# Memory_schematic.net
KiCad netlist of a schematic drawn in Altium Designer
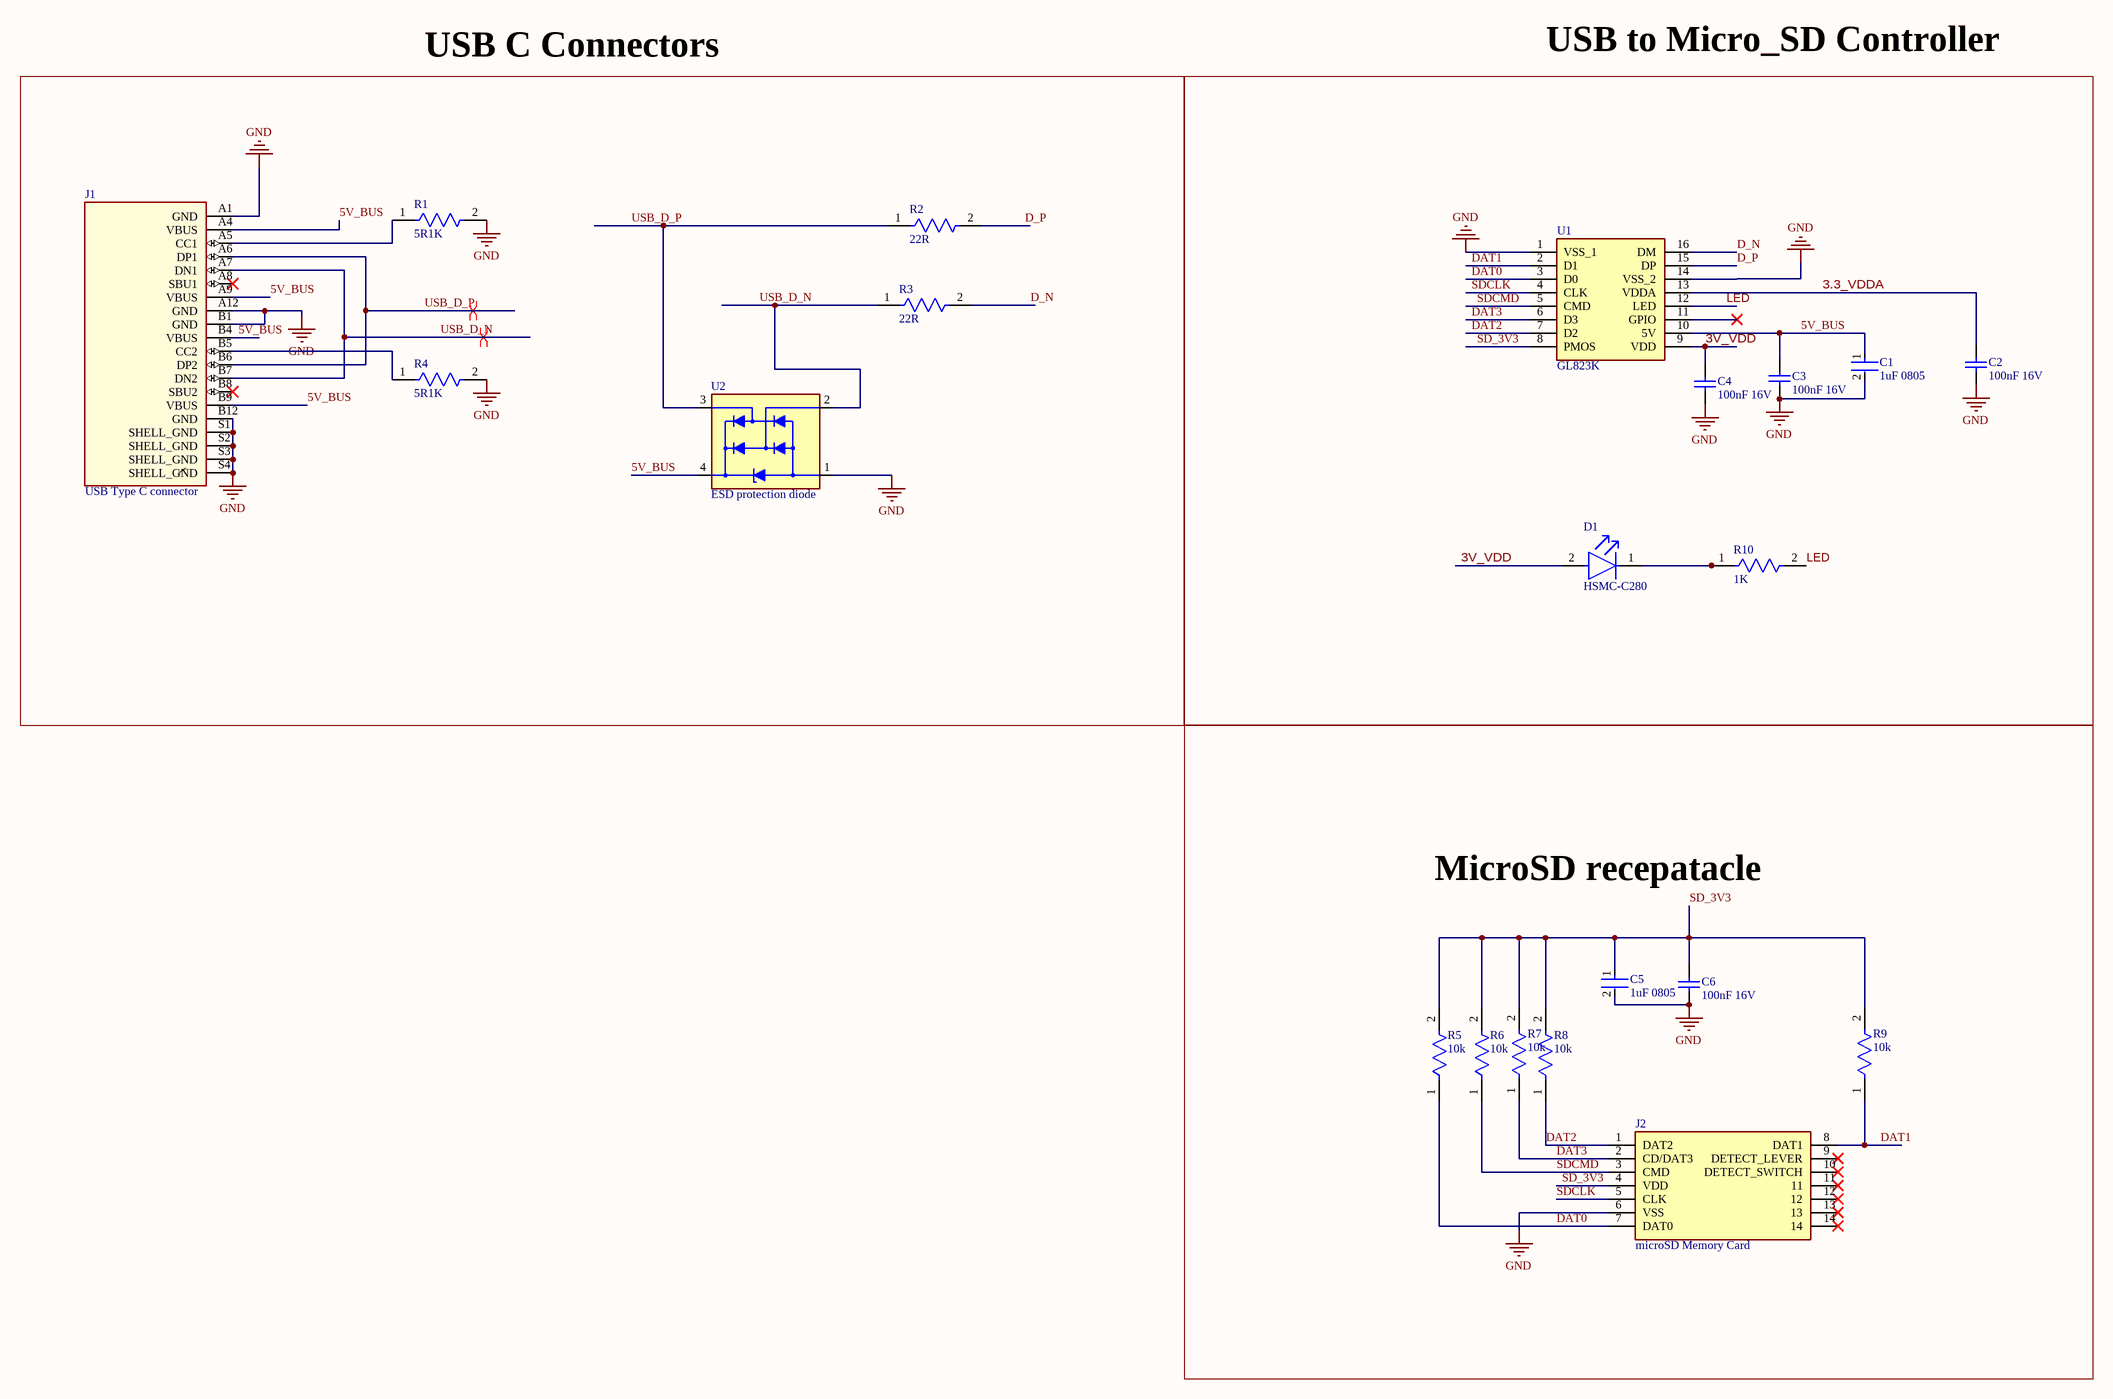
[diagram p0: Memory_schematic.SchDoc]

(export (version "E")
  (design (tool "Eeschema 10.0.6"))
  (components
    (comp (ref "C1")
      (value "1uF 0805")
      (footprint "FP-CC0805-0_85-MFG")
      (description "CC0805 1 uF X7R 10.00% 16 V")
      (fields
        (field (name "OCTOPART") "https://octopart.com/cc0805kfx7r7bb105-yageo-30261725")
        (field (name "MANUFACTURER") "Yageo")
      )
      (libsource (lib "Altium Content Vault") (part "11868f565c42a9108669ba33697ecf6"))
    )
    (comp (ref "C2")
      (value "100nF 16V")
      (footprint "CAPC0805(2012)145_M")
      (description "CAP 100nF 16V ±5% 0805 (2012 Metric) Thickness 1.45mm SMD")
      (fields (field (name "TOLERANCE") "Â±5%"))
      (libsource (lib "Altium Content Vault") (part "CAP"))
    )
    (comp (ref "C3")
      (value "100nF 16V")
      (footprint "CAPC0805(2012)145_M")
      (description "CAP 100nF 16V ±5% 0805 (2012 Metric) Thickness 1.45mm SMD")
      (fields (field (name "TOLERANCE") "Â±5%"))
      (libsource (lib "Altium Content Vault") (part "CAP"))
    )
    (comp (ref "C4")
      (value "100nF 16V")
      (footprint "CAPC0805(2012)145_M")
      (description "CAP 100nF 16V ±5% 0805 (2012 Metric) Thickness 1.45mm SMD")
      (fields (field (name "TOLERANCE") "Â±5%"))
      (libsource (lib "Altium Content Vault") (part "CAP"))
    )
    (comp (ref "C5")
      (value "1uF 0805")
      (footprint "FP-CC0805-0_85-MFG")
      (description "CC0805 1 uF X7R 10.00% 16 V")
      (fields
        (field (name "OCTOPART") "https://octopart.com/cc0805kfx7r7bb105-yageo-30261725")
        (field (name "MANUFACTURER") "Yageo")
      )
      (libsource (lib "Altium Content Vault") (part "11868f565c42a9108669ba33697ecf6"))
    )
    (comp (ref "C6")
      (value "100nF 16V")
      (footprint "CAPC0805(2012)145_M")
      (description "CAP 100nF 16V ±5% 0805 (2012 Metric) Thickness 1.45mm SMD")
      (fields (field (name "TOLERANCE") "Â±5%"))
      (libsource (lib "Altium Content Vault") (part "CAP"))
    )
    (comp (ref "D1")
      (value "HSMC-C280")
      (footprint "FP-HSMC-C280-MFG")
      (description "LED RED DIFFUSED 0402 SMD")
      (libsource (lib "Altium Content Vault") (part "8706943c75ba83719d021d2fdc84c58"))
    )
    (comp (ref "J1")
      (value "USB Type C connector")
      (footprint "CONN16_C16PIN_SHN")
      (description "https://jlcpcb.com/partdetail/ShouHan-TYPE_C_16PIN_2MD_073/C2765186?utm_source=chatgpt.com")
      (libsource (lib "Memory_card_reader_Schlib1") (part "TYPE-C 16PIN 2MD(073) SHOU HAN"))
    )
    (comp (ref "J2")
      (value "microSD Memory Card")
      (footprint "5033981892")
      (fields (field (name "MANUFACTURER") "Molex") (field (name "MANUFACTURER PART NUMBER") "503398-1892"))
      (libsource (lib "Memory_card_reader_Schlib1") (part "503398-1892"))
    )
    (comp (ref "R1")
      (value "5R1K")
      (footprint "FP-RN73R2A-IPC_C")
      (description "5.1kΩ ±0.05% 0.125W, 1/8W Chip Resistor 0805 (2012 Metric) Moisture Resistant Thin Film")
      (libsource (lib "Altium Content Vault") (part "1029c3af85768c4190bb7ad29bc67b5"))
    )
    (comp (ref "R2")
      (value "22R")
      (footprint "FP-RT0805-MFG")
      (description "RES SMD 22 OHM 1% 1/8W 0805")
      (fields
        (field (name "MANUFACTURER") "Yageo")
        (field (name "MANUFACTURER PART NUMBER") "RT0805FRD0722RL")
      )
      (libsource (lib "Altium Content Vault") (part "1029c3af85768c4190bb7ad29bc67b5"))
    )
    (comp (ref "R3")
      (value "22R")
      (footprint "FP-RT0805-MFG")
      (description "RES SMD 22 OHM 1% 1/8W 0805")
      (fields
        (field (name "MANUFACTURER") "Yageo")
        (field (name "MANUFACTURER PART NUMBER") "RT0805FRD0722RL")
      )
      (libsource (lib "Altium Content Vault") (part "1029c3af85768c4190bb7ad29bc67b5"))
    )
    (comp (ref "R4")
      (value "5R1K")
      (footprint "FP-RN73R2A-IPC_C")
      (description "5.1kΩ ±0.05% 0.125W, 1/8W Chip Resistor 0805 (2012 Metric) Moisture Resistant Thin Film")
      (libsource (lib "Altium Content Vault") (part "1029c3af85768c4190bb7ad29bc67b5"))
    )
    (comp (ref "R5")
      (value "10k")
      (footprint "FP-CRGP0805-IPC_C")
      (description "CRGP 0805 10K 1% CRGP0805F10K")
      (fields (field (name "MANUFACTURER PART NUMBER") "CRGP0805F10K") (field (name "MANUFACTURER") "TE"))
      (libsource (lib "Altium Content Vault") (part "1029c3af85768c4190bb7ad29bc67b5"))
    )
    (comp (ref "R6")
      (value "10k")
      (footprint "FP-CRGP0805-IPC_C")
      (description "CRGP 0805 10K 1% CRGP0805F10K")
      (fields (field (name "MANUFACTURER PART NUMBER") "CRGP0805F10K") (field (name "MANUFACTURER") "TE"))
      (libsource (lib "Altium Content Vault") (part "1029c3af85768c4190bb7ad29bc67b5"))
    )
    (comp (ref "R7")
      (value "10k")
      (footprint "FP-CRGP0805-IPC_C")
      (description "CRGP 0805 10K 1% CRGP0805F10K")
      (fields (field (name "MANUFACTURER PART NUMBER") "CRGP0805F10K") (field (name "MANUFACTURER") "TE"))
      (libsource (lib "Altium Content Vault") (part "1029c3af85768c4190bb7ad29bc67b5"))
    )
    (comp (ref "R8")
      (value "10k")
      (footprint "FP-CRGP0805-IPC_C")
      (description "CRGP 0805 10K 1% CRGP0805F10K")
      (fields (field (name "MANUFACTURER PART NUMBER") "CRGP0805F10K") (field (name "MANUFACTURER") "TE"))
      (libsource (lib "Altium Content Vault") (part "1029c3af85768c4190bb7ad29bc67b5"))
    )
    (comp (ref "R9")
      (value "10k")
      (footprint "FP-CRGP0805-IPC_C")
      (description "CRGP 0805 10K 1% CRGP0805F10K")
      (fields (field (name "MANUFACTURER PART NUMBER") "CRGP0805F10K") (field (name "MANUFACTURER") "TE"))
      (libsource (lib "Altium Content Vault") (part "1029c3af85768c4190bb7ad29bc67b5"))
    )
    (comp (ref "R10")
      (value "1K")
      (footprint "FP-RN73R2A-IPC_A")
      (description "1kΩ ±0.1% 0.125W, 1/8W Chip Resistor 0805 (2012 Metric) Moisture Resistant Thin Film")
      (libsource (lib "Altium Content Vault") (part "1029c3af85768c4190bb7ad29bc67b5"))
    )
    (comp (ref "U1")
      (value "GL823K")
      (footprint "SOP64P600X175-16N")
      (description "USB 2.0 card reader controller")
      (libsource (lib "Memory_card_reader_Schlib1") (part "GL823K-HCY04"))
    )
    (comp (ref "U2")
      (value "ESD protection diode")
      (footprint "SOT190P230X110-4N")
      (description "PRTR Series 9 V 1 pF Rail-to-Rail ESD Protection Diode - SOT-143B")
      (fields
        (field (name "MANUFACTURER") "Nexperia")
        (field (name "MANUFACTURER PART NUMBER") "PRTR5V0U2X,215")
      )
      (libsource (lib "Memory_card_reader_Schlib1") (part "PRTR5V0U2X,215"))
    )
  )
  (nets
    (net (code "1") (name "/3.3_VDDA") (class "Default")
      (node (ref "C2") (pin "2") (pinfunction "2_2") (pintype "passive"))
      (node (ref "U1") (pin "13") (pinfunction "VDDA_13") (pintype "passive"))
    )
    (net (code "2") (name "/3V_VDD") (class "Default")
      (node (ref "C4") (pin "2") (pinfunction "2_2") (pintype "passive"))
      (node (ref "D1") (pin "2") (pinfunction "A_2") (pintype "passive"))
      (node (ref "U1") (pin "9") (pinfunction "VDD_9") (pintype "passive"))
    )
    (net (code "3") (name "/5V_BUS") (class "Default")
      (node (ref "C1") (pin "1") (pinfunction "1_1") (pintype "passive"))
      (node (ref "C3") (pin "2") (pinfunction "2_2") (pintype "passive"))
      (node (ref "J1") (pin "A4") (pinfunction "VBUS_A4") (pintype "power_in"))
      (node (ref "J1") (pin "A9") (pinfunction "VBUS_A9") (pintype "power_in"))
      (node (ref "J1") (pin "B4") (pinfunction "VBUS_B4") (pintype "power_in"))
      (node (ref "J1") (pin "B9") (pinfunction "VBUS_B9") (pintype "power_in"))
      (node (ref "U1") (pin "10") (pinfunction "5V_10") (pintype "passive"))
      (node (ref "U2") (pin "4") (pinfunction "VCC_4") (pintype "passive"))
    )
    (net (code "4") (name "/DAT0") (class "Default")
      (node (ref "J2") (pin "7") (pinfunction "DAT0_7") (pintype "passive"))
      (node (ref "R5") (pin "1") (pinfunction "1_1") (pintype "passive"))
      (node (ref "U1") (pin "3") (pinfunction "D0_3") (pintype "passive"))
    )
    (net (code "5") (name "/DAT1") (class "Default")
      (node (ref "J2") (pin "8") (pinfunction "DAT1_8") (pintype "passive"))
      (node (ref "R9") (pin "1") (pinfunction "1_1") (pintype "passive"))
      (node (ref "U1") (pin "2") (pinfunction "D1_2") (pintype "passive"))
    )
    (net (code "6") (name "/DAT2") (class "Default")
      (node (ref "J2") (pin "1") (pinfunction "DAT2_1") (pintype "passive"))
      (node (ref "R8") (pin "1") (pinfunction "1_1") (pintype "passive"))
      (node (ref "U1") (pin "7") (pinfunction "D2_7") (pintype "passive"))
    )
    (net (code "7") (name "/DAT3") (class "Default")
      (node (ref "J2") (pin "2") (pinfunction "CD/DAT3_2") (pintype "passive"))
      (node (ref "R7") (pin "1") (pinfunction "1_1") (pintype "passive"))
      (node (ref "U1") (pin "6") (pinfunction "D3_6") (pintype "passive"))
    )
    (net (code "8") (name "/D_N") (class "Default")
      (node (ref "R3") (pin "2") (pinfunction "2_2") (pintype "passive"))
      (node (ref "U1") (pin "16") (pinfunction "DM_16") (pintype "passive"))
    )
    (net (code "9") (name "/D_P") (class "Default")
      (node (ref "R2") (pin "2") (pinfunction "2_2") (pintype "passive"))
      (node (ref "U1") (pin "15") (pinfunction "DP_15") (pintype "passive"))
    )
    (net (code "10") (name "/LED") (class "Default")
      (node (ref "R10") (pin "2") (pinfunction "2_2") (pintype "passive"))
      (node (ref "U1") (pin "12") (pinfunction "LED_12") (pintype "passive"))
    )
    (net (code "11") (name "/SDCLK") (class "Default")
      (node (ref "J2") (pin "5") (pinfunction "CLK_5") (pintype "passive"))
      (node (ref "U1") (pin "4") (pinfunction "CLK_4") (pintype "passive"))
    )
    (net (code "12") (name "/SDCMD") (class "Default")
      (node (ref "J2") (pin "3") (pinfunction "CMD_3") (pintype "passive"))
      (node (ref "R6") (pin "1") (pinfunction "1_1") (pintype "passive"))
      (node (ref "U1") (pin "5") (pinfunction "CMD_5") (pintype "passive"))
    )
    (net (code "13") (name "/SD_3V3") (class "Default")
      (node (ref "C5") (pin "1") (pinfunction "1_1") (pintype "passive"))
      (node (ref "C6") (pin "2") (pinfunction "2_2") (pintype "passive"))
      (node (ref "J2") (pin "4") (pinfunction "VDD_4") (pintype "passive"))
      (node (ref "R5") (pin "2") (pinfunction "2_2") (pintype "passive"))
      (node (ref "R6") (pin "2") (pinfunction "2_2") (pintype "passive"))
      (node (ref "R7") (pin "2") (pinfunction "2_2") (pintype "passive"))
      (node (ref "R8") (pin "2") (pinfunction "2_2") (pintype "passive"))
      (node (ref "R9") (pin "2") (pinfunction "2_2") (pintype "passive"))
      (node (ref "U1") (pin "8") (pinfunction "PMOS_8") (pintype "passive"))
    )
    (net (code "14") (name "/USB_D_N") (class "Default")
      (node (ref "J1") (pin "A7") (pinfunction "DN1_A7") (pintype "bidirectional"))
      (node (ref "J1") (pin "B7") (pinfunction "DN2_B7") (pintype "bidirectional"))
      (node (ref "R3") (pin "1") (pinfunction "1_1") (pintype "passive"))
      (node (ref "U2") (pin "2") (pinfunction "I/O_1_2") (pintype "passive"))
    )
    (net (code "15") (name "/USB_D_P") (class "Default")
      (node (ref "J1") (pin "A6") (pinfunction "DP1_A6") (pintype "bidirectional"))
      (node (ref "J1") (pin "B6") (pinfunction "DP2_B6") (pintype "bidirectional"))
      (node (ref "R2") (pin "1") (pinfunction "1_1") (pintype "passive"))
      (node (ref "U2") (pin "3") (pinfunction "I/O_2_3") (pintype "passive"))
    )
    (net (code "16") (name "GND") (class "Default")
      (node (ref "C1") (pin "2") (pinfunction "2_2") (pintype "passive"))
      (node (ref "C2") (pin "1") (pinfunction "1_1") (pintype "passive"))
      (node (ref "C3") (pin "1") (pinfunction "1_1") (pintype "passive"))
      (node (ref "C4") (pin "1") (pinfunction "1_1") (pintype "passive"))
      (node (ref "C5") (pin "2") (pinfunction "2_2") (pintype "passive"))
      (node (ref "C6") (pin "1") (pinfunction "1_1") (pintype "passive"))
      (node (ref "J1") (pin "A1") (pinfunction "GND_A1") (pintype "power_in"))
      (node (ref "J1") (pin "A12") (pinfunction "GND_A12") (pintype "power_in"))
      (node (ref "J1") (pin "B1") (pinfunction "GND_B1") (pintype "power_in"))
      (node (ref "J1") (pin "B12") (pinfunction "GND_B12") (pintype "power_in"))
      (node (ref "J1") (pin "S1") (pinfunction "SHELL_GND_S1") (pintype "power_in"))
      (node (ref "J1") (pin "S2") (pinfunction "SHELL_GND_S2") (pintype "power_in"))
      (node (ref "J1") (pin "S3") (pinfunction "SHELL_GND_S3") (pintype "power_in"))
      (node (ref "J1") (pin "S4") (pinfunction "SHELL_GND_S4") (pintype "power_in"))
      (node (ref "J2") (pin "6") (pinfunction "VSS_6") (pintype "passive"))
      (node (ref "R1") (pin "2") (pinfunction "2_2") (pintype "passive"))
      (node (ref "R4") (pin "2") (pinfunction "2_2") (pintype "passive"))
      (node (ref "U1") (pin "1") (pinfunction "VSS_1_1") (pintype "passive"))
      (node (ref "U1") (pin "14") (pinfunction "VSS_2_14") (pintype "passive"))
      (node (ref "U2") (pin "1") (pinfunction "GND_1") (pintype "passive"))
    )
    (net (code "17") (name "Net-(D1-C)") (class "Default")
      (node (ref "D1") (pin "1") (pinfunction "C_1") (pintype "passive"))
      (node (ref "R10") (pin "1") (pinfunction "1_1") (pintype "passive"))
    )
    (net (code "18") (name "Net-(J1-CC1)") (class "Default")
      (node (ref "J1") (pin "A5") (pinfunction "CC1_A5") (pintype "bidirectional"))
      (node (ref "R1") (pin "1") (pinfunction "1_1") (pintype "passive"))
    )
    (net (code "19") (name "Net-(J1-CC2)") (class "Default")
      (node (ref "J1") (pin "B5") (pinfunction "CC2_B5") (pintype "bidirectional"))
      (node (ref "R4") (pin "1") (pinfunction "1_1") (pintype "passive"))
    )
    (net (code "20") (name "unconnected-(J1-SBU1-PadA8)") (class "Default")
      (node (ref "J1") (pin "A8") (pinfunction "SBU1_A8") (pintype "bidirectional+no_connect"))
    )
    (net (code "21") (name "unconnected-(J1-SBU2-PadB8)") (class "Default")
      (node (ref "J1") (pin "B8") (pinfunction "SBU2_B8") (pintype "bidirectional+no_connect"))
    )
    (net (code "22") (name "unconnected-(J2-DETECT_LEVER-Pad9)") (class "Default")
      (node (ref "J2") (pin "9") (pinfunction "DETECT_LEVER_9") (pintype "passive+no_connect"))
    )
    (net (code "23") (name "unconnected-(J2-DETECT_SWITCH-Pad10)") (class "Default")
      (node (ref "J2") (pin "10") (pinfunction "DETECT_SWITCH_10") (pintype "passive+no_connect"))
    )
    (net (code "24") (name "unconnected-(J2-Pad11)") (class "Default")
      (node (ref "J2") (pin "11") (pinfunction "11_11") (pintype "passive+no_connect"))
    )
    (net (code "25") (name "unconnected-(J2-Pad12)") (class "Default")
      (node (ref "J2") (pin "12") (pinfunction "12_12") (pintype "passive+no_connect"))
    )
    (net (code "26") (name "unconnected-(J2-Pad13)") (class "Default")
      (node (ref "J2") (pin "13") (pinfunction "13_13") (pintype "passive+no_connect"))
    )
    (net (code "27") (name "unconnected-(J2-Pad14)") (class "Default")
      (node (ref "J2") (pin "14") (pinfunction "14_14") (pintype "passive+no_connect"))
    )
    (net (code "28") (name "unconnected-(U1-GPIO-Pad11)") (class "Default")
      (node (ref "U1") (pin "11") (pinfunction "GPIO_11") (pintype "passive+no_connect"))
    )
  )
)
